# Gator_Log.net
KiCad netlist of a schematic drawn in EAGLE
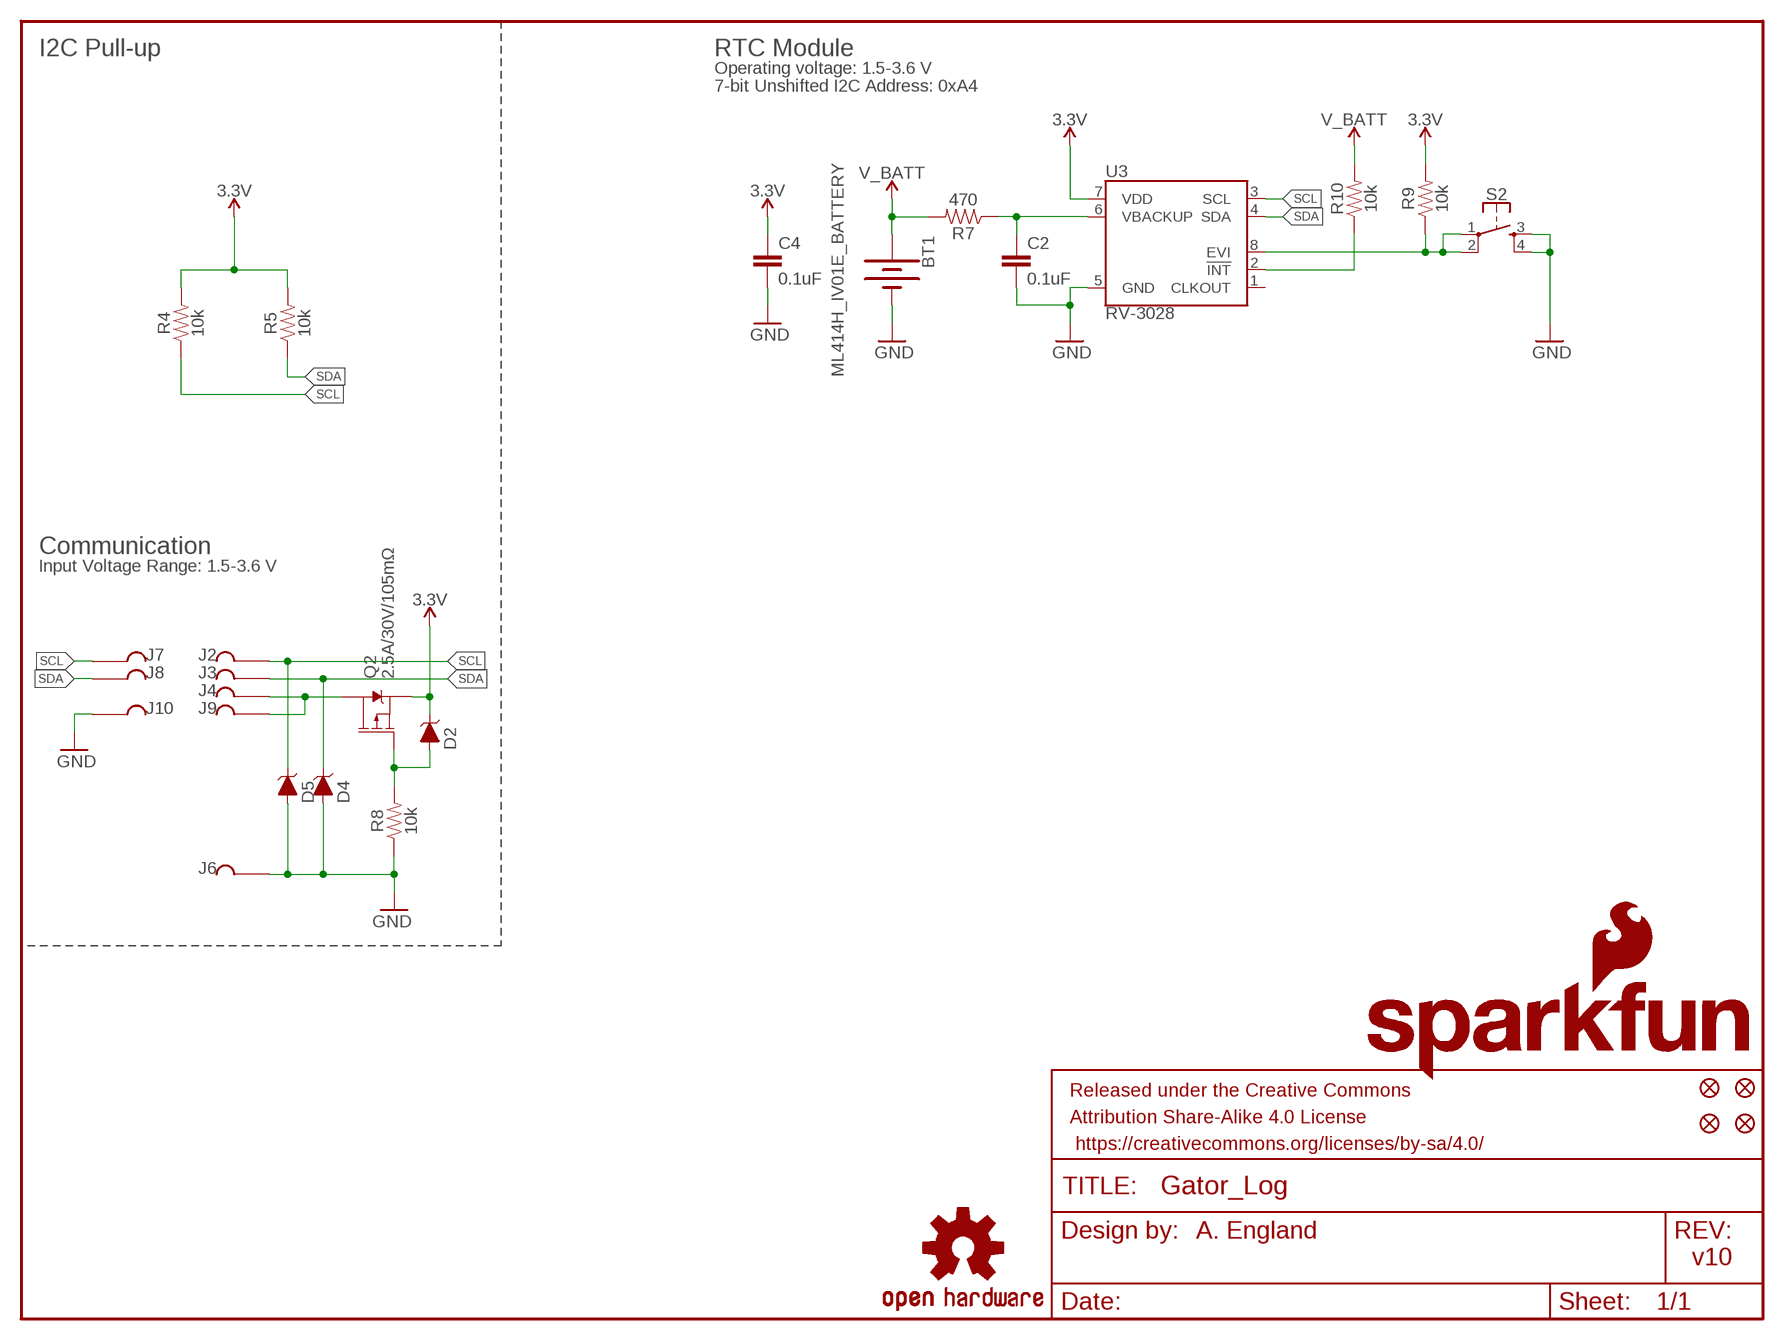
[diagram p0: schematic, sheet 1]

(export (version "E")
  (design (tool "Eeschema 10.0.6"))
  (components
    (comp (ref "BT1")
      (value "ML414H_IV01E_BATTERY")
      (footprint "eagle-import:ML414H_IV01E")
      (libsource (lib "eagle-import") (part "ML414H_IV01E_BATTERY"))
    )
    (comp (ref "C2")
      (value "0.1uF")
      (footprint "eagle-import:0603")
      (libsource (lib "eagle-import") (part "0.1UF-0603-25V-(+80/-20%)"))
    )
    (comp (ref "C4")
      (value "0.1uF")
      (footprint "eagle-import:0603")
      (libsource (lib "eagle-import") (part "0.1UF-0603-25V-(+80/-20%)"))
    )
    (comp (ref "D2")
      (value "3.6V")
      (footprint "eagle-import:SOD-323")
      (libsource (lib "eagle-import") (part "DIODE-ZENER-BZT52C3V6S"))
    )
    (comp (ref "D4")
      (value "3.6V")
      (footprint "eagle-import:SOD-323")
      (libsource (lib "eagle-import") (part "DIODE-ZENER-BZT52C3V6S"))
    )
    (comp (ref "D5")
      (value "3.6V")
      (footprint "eagle-import:SOD-323")
      (libsource (lib "eagle-import") (part "DIODE-ZENER-BZT52C3V6S"))
    )
    (comp (ref "FID1")
      (value "FIDUCIALUFIDUCIAL")
      (footprint "eagle-import:FIDUCIAL-MICRO")
      (libsource (lib "eagle-import") (part "FIDUCIALUFIDUCIAL"))
    )
    (comp (ref "FID2")
      (value "FIDUCIALUFIDUCIAL")
      (footprint "eagle-import:FIDUCIAL-MICRO")
      (libsource (lib "eagle-import") (part "FIDUCIALUFIDUCIAL"))
    )
    (comp (ref "FID3")
      (value "FIDUCIALUFIDUCIAL")
      (footprint "eagle-import:FIDUCIAL-MICRO")
      (libsource (lib "eagle-import") (part "FIDUCIALUFIDUCIAL"))
    )
    (comp (ref "FID4")
      (value "FIDUCIALUFIDUCIAL")
      (footprint "eagle-import:FIDUCIAL-MICRO")
      (libsource (lib "eagle-import") (part "FIDUCIALUFIDUCIAL"))
    )
    (comp (ref "FRAME1")
      (value "FRAME-LETTER")
      (footprint "eagle-import:CREATIVE_COMMONS")
      (libsource (lib "eagle-import") (part "FRAME-LETTER"))
    )
    (comp (ref "J2")
      (value "GATORGATOR_MINI")
      (footprint "eagle-import:GATOR_MINI")
      (libsource (lib "eagle-import") (part "GATORGATOR_MINI"))
    )
    (comp (ref "J3")
      (value "GATORGATOR_MINI")
      (footprint "eagle-import:GATOR_MINI")
      (libsource (lib "eagle-import") (part "GATORGATOR_MINI"))
    )
    (comp (ref "J4")
      (value "GATORGATOR_MINI")
      (footprint "eagle-import:GATOR_MINI")
      (libsource (lib "eagle-import") (part "GATORGATOR_MINI"))
    )
    (comp (ref "J6")
      (value "GATORGATOR_MINI")
      (footprint "eagle-import:GATOR_MINI")
      (libsource (lib "eagle-import") (part "GATORGATOR_MINI"))
    )
    (comp (ref "J7")
      (value "GATORGATOR_MINI")
      (footprint "eagle-import:GATOR_MINI")
      (libsource (lib "eagle-import") (part "GATORGATOR_MINI"))
    )
    (comp (ref "J8")
      (value "GATORGATOR_MINI")
      (footprint "eagle-import:GATOR_MINI")
      (libsource (lib "eagle-import") (part "GATORGATOR_MINI"))
    )
    (comp (ref "J9")
      (value "GATORGATOR_MINI")
      (footprint "eagle-import:GATOR_MINI")
      (libsource (lib "eagle-import") (part "GATORGATOR_MINI"))
    )
    (comp (ref "J10")
      (value "GATORGATOR_MINI")
      (footprint "eagle-import:GATOR_MINI")
      (libsource (lib "eagle-import") (part "GATORGATOR_MINI"))
    )
    (comp (ref "LOGO1")
      (value "SFE_LOGO_FLAME.1_INCH")
      (footprint "eagle-import:SFE_LOGO_FLAME_.1")
      (libsource (lib "eagle-import") (part "SFE_LOGO_FLAME.1_INCH"))
    )
    (comp (ref "LOGO2")
      (value "OSHW-LOGOMINI")
      (footprint "eagle-import:OSHW-LOGO-MINI")
      (libsource (lib "eagle-import") (part "OSHW-LOGOMINI"))
    )
    (comp (ref "LOGO4")
      (value "SFE_LOGO_NAME_FLAME.1_INCH")
      (footprint "eagle-import:SFE_LOGO_NAME_FLAME_.1")
      (libsource (lib "eagle-import") (part "SFE_LOGO_NAME_FLAME.1_INCH"))
    )
    (comp (ref "Q2")
      (value "2.5A/30V/105mΩ")
      (footprint "eagle-import:SOT23-3")
      (libsource (lib "eagle-import") (part "MOSFET_PCH-DMG2307L"))
    )
    (comp (ref "R4")
      (value "10k")
      (footprint "eagle-import:0603")
      (libsource (lib "eagle-import") (part "10KOHM-0603-1/10W-1%"))
    )
    (comp (ref "R5")
      (value "10k")
      (footprint "eagle-import:0603")
      (libsource (lib "eagle-import") (part "10KOHM-0603-1/10W-1%"))
    )
    (comp (ref "R7")
      (value "470")
      (footprint "eagle-import:0603")
      (libsource (lib "eagle-import") (part "470OHM-0603-1/10W-1%"))
    )
    (comp (ref "R8")
      (value "10k")
      (footprint "eagle-import:0603")
      (libsource (lib "eagle-import") (part "10KOHM-0603-1/10W-1%"))
    )
    (comp (ref "R9")
      (value "10k")
      (footprint "eagle-import:0603")
      (libsource (lib "eagle-import") (part "10KOHM-0603-1/10W-1%"))
    )
    (comp (ref "R10")
      (value "10k")
      (footprint "eagle-import:0603")
      (libsource (lib "eagle-import") (part "10KOHM-0603-1/10W-1%"))
    )
    (comp (ref "S2")
      (value "MOMENTARY-SWITCH-SPST-2-SMD-5.2MM-TALL")
      (footprint "eagle-import:TACTILE_SWITCH_SMD_5.2MM")
      (libsource (lib "eagle-import") (part "MOMENTARY-SWITCH-SPST-2-SMD-5.2MM-TALL"))
    )
    (comp (ref "U3")
      (value "RV-3028")
      (footprint "eagle-import:RV-3028")
      (libsource (lib "eagle-import") (part "RV-3028"))
    )
  )
  (nets
    (net (code "1") (name "3.3V") (class "Default")
      (node (ref "C4") (pin "1") (pinfunction "1_1") (pintype "passive"))
      (node (ref "D2") (pin "C") (pinfunction "C_C") (pintype "passive"))
      (node (ref "Q2") (pin "2") (pinfunction "S_2") (pintype "bidirectional"))
      (node (ref "R4") (pin "2") (pinfunction "2_2") (pintype "passive"))
      (node (ref "R5") (pin "2") (pinfunction "2_2") (pintype "passive"))
      (node (ref "R9") (pin "2") (pinfunction "2_2") (pintype "passive"))
      (node (ref "U3") (pin "7") (pinfunction "VDD_7") (pintype "bidirectional"))
    )
    (net (code "2") (name "GND") (class "Default")
      (node (ref "BT1") (pin "-") (pinfunction "-_-") (pintype "power_in"))
      (node (ref "C2") (pin "2") (pinfunction "2_2") (pintype "passive"))
      (node (ref "C4") (pin "2") (pinfunction "2_2") (pintype "passive"))
      (node (ref "D4") (pin "A") (pinfunction "A_A") (pintype "passive"))
      (node (ref "D5") (pin "A") (pinfunction "A_A") (pintype "passive"))
      (node (ref "J10") (pin "P$2") (pinfunction "P$1_P$2") (pintype "bidirectional"))
      (node (ref "J6") (pin "P$2") (pinfunction "P$1_P$2") (pintype "bidirectional"))
      (node (ref "R8") (pin "1") (pinfunction "1_1") (pintype "passive"))
      (node (ref "S2") (pin "3") (pinfunction "3_3") (pintype "passive"))
      (node (ref "S2") (pin "4") (pinfunction "4_4") (pintype "passive"))
      (node (ref "U3") (pin "5") (pinfunction "GND_5") (pintype "bidirectional"))
    )
    (net (code "3") (name "Net-(J4-P$1)") (class "Default")
      (node (ref "J4") (pin "P$2") (pinfunction "P$1_P$2") (pintype "bidirectional"))
      (node (ref "J9") (pin "P$2") (pinfunction "P$1_P$2") (pintype "bidirectional"))
      (node (ref "Q2") (pin "3") (pinfunction "D_3") (pintype "bidirectional"))
    )
    (net (code "4") (name "Net-(Q2-G)") (class "Default")
      (node (ref "D2") (pin "A") (pinfunction "A_A") (pintype "passive"))
      (node (ref "Q2") (pin "1") (pinfunction "G_1") (pintype "bidirectional"))
      (node (ref "R8") (pin "2") (pinfunction "2_2") (pintype "passive"))
    )
    (net (code "5") (name "Net-(U3-EVI)") (class "Default")
      (node (ref "R9") (pin "1") (pinfunction "1_1") (pintype "passive"))
      (node (ref "S2") (pin "1") (pinfunction "1_1") (pintype "passive"))
      (node (ref "S2") (pin "2") (pinfunction "2_2") (pintype "passive"))
      (node (ref "U3") (pin "8") (pinfunction "EVI_8") (pintype "bidirectional"))
    )
    (net (code "6") (name "Net-(U3-VBACKUP)") (class "Default")
      (node (ref "C2") (pin "1") (pinfunction "1_1") (pintype "passive"))
      (node (ref "R7") (pin "1") (pinfunction "1_1") (pintype "passive"))
      (node (ref "U3") (pin "6") (pinfunction "VBACKUP_6") (pintype "bidirectional"))
    )
    (net (code "7") (name "Net-(U3-~{INT})") (class "Default")
      (node (ref "R10") (pin "1") (pinfunction "1_1") (pintype "passive"))
      (node (ref "U3") (pin "2") (pinfunction "~{INT}_2") (pintype "bidirectional"))
    )
    (net (code "8") (name "SCL") (class "Default")
      (node (ref "D5") (pin "C") (pinfunction "C_C") (pintype "passive"))
      (node (ref "J2") (pin "P$2") (pinfunction "P$1_P$2") (pintype "bidirectional"))
      (node (ref "J7") (pin "P$2") (pinfunction "P$1_P$2") (pintype "bidirectional"))
      (node (ref "R4") (pin "1") (pinfunction "1_1") (pintype "passive"))
      (node (ref "U3") (pin "3") (pinfunction "SCL_3") (pintype "bidirectional"))
    )
    (net (code "9") (name "SDA") (class "Default")
      (node (ref "D4") (pin "C") (pinfunction "C_C") (pintype "passive"))
      (node (ref "J3") (pin "P$2") (pinfunction "P$1_P$2") (pintype "bidirectional"))
      (node (ref "J8") (pin "P$2") (pinfunction "P$1_P$2") (pintype "bidirectional"))
      (node (ref "R5") (pin "1") (pinfunction "1_1") (pintype "passive"))
      (node (ref "U3") (pin "4") (pinfunction "SDA_4") (pintype "bidirectional"))
    )
    (net (code "10") (name "V_BATT") (class "Default")
      (node (ref "BT1") (pin "+") (pinfunction "+_+") (pintype "power_in"))
      (node (ref "R10") (pin "2") (pinfunction "2_2") (pintype "passive"))
      (node (ref "R7") (pin "2") (pinfunction "2_2") (pintype "passive"))
    )
    (net (code "11") (name "unconnected-(U3-CLKOUT-Pad1)") (class "Default")
      (node (ref "U3") (pin "1") (pinfunction "CLKOUT_1") (pintype "bidirectional"))
    )
  )
)
